# IRGate.net
KiCad netlist of a schematic drawn in EAGLE
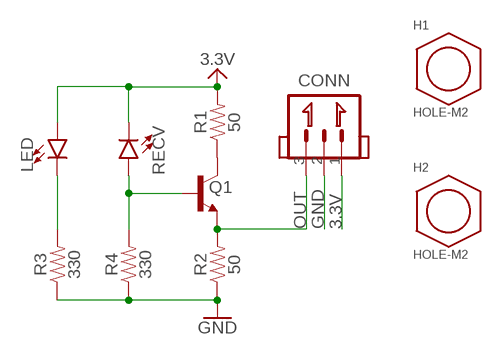
[diagram p0: schematic, sheet 1]

(export (version "E")
  (design (tool "Eeschema 10.0.6"))
  (components
    (comp (ref "CONN")
      (value "JST_1.25_3P")
      (footprint "eagle-import:JST1.25_3P")
      (libsource (lib "eagle-import") (part "JST_1.25_3P"))
    )
    (comp (ref "H1")
      (value "HOLE-M2")
      (footprint "eagle-import:M2")
      (libsource (lib "eagle-import") (part "HOLE-M2"))
    )
    (comp (ref "H2")
      (value "HOLE-M2")
      (footprint "eagle-import:M2")
      (libsource (lib "eagle-import") (part "HOLE-M2"))
    )
    (comp (ref "LED")
      (value "LED-IRTSAL6100")
      (footprint "eagle-import:LED_5MM")
      (libsource (lib "eagle-import") (part "LED-IRTSAL6100"))
    )
    (comp (ref "Q1")
      (value "NPNSOT23-3")
      (footprint "eagle-import:SOT23-3")
      (libsource (lib "eagle-import") (part "NPNSOT23-3"))
    )
    (comp (ref "R1")
      (value "50")
      (footprint "eagle-import:0603")
      (libsource (lib "eagle-import") (part "RESISTOR0603"))
    )
    (comp (ref "R2")
      (value "50")
      (footprint "eagle-import:0603")
      (libsource (lib "eagle-import") (part "RESISTOR0603"))
    )
    (comp (ref "R3")
      (value "330")
      (footprint "eagle-import:0603")
      (libsource (lib "eagle-import") (part "RESISTOR0603"))
    )
    (comp (ref "R4")
      (value "330")
      (footprint "eagle-import:0603")
      (libsource (lib "eagle-import") (part "RESISTOR0603"))
    )
    (comp (ref "RECV")
      (value "LED-IRSIDE_EMITTER")
      (footprint "eagle-import:LTE-302")
      (libsource (lib "eagle-import") (part "LED-IRSIDE_EMITTER"))
    )
  )
  (nets
    (net (code "1") (name "/OUT") (class "Default")
      (node (ref "CONN") (pin "3") (pinfunction "3_3") (pintype "passive"))
      (node (ref "Q1") (pin "2") (pinfunction "E_2") (pintype "passive"))
      (node (ref "R2") (pin "2") (pinfunction "2_2") (pintype "passive"))
    )
    (net (code "2") (name "Net-(LED-C)") (class "Default")
      (node (ref "LED") (pin "K") (pinfunction "C_K") (pintype "passive"))
      (node (ref "R3") (pin "2") (pinfunction "2_2") (pintype "passive"))
    )
    (net (code "3") (name "Net-(Q1-B)") (class "Default")
      (node (ref "Q1") (pin "1") (pinfunction "B_1") (pintype "passive"))
      (node (ref "R4") (pin "2") (pinfunction "2_2") (pintype "passive"))
      (node (ref "RECV") (pin "A") (pinfunction "A_A") (pintype "passive"))
    )
    (net (code "4") (name "Net-(Q1-C)") (class "Default")
      (node (ref "Q1") (pin "3") (pinfunction "C_3") (pintype "passive"))
      (node (ref "R1") (pin "1") (pinfunction "1_1") (pintype "passive"))
    )
    (net (code "5") (name "SUPPLY_3.3V") (class "Default")
      (node (ref "CONN") (pin "1") (pinfunction "1_1") (pintype "passive"))
      (node (ref "LED") (pin "A") (pinfunction "A_A") (pintype "passive"))
      (node (ref "R1") (pin "2") (pinfunction "2_2") (pintype "passive"))
      (node (ref "RECV") (pin "C") (pinfunction "C_C") (pintype "passive"))
    )
    (net (code "6") (name "SUPPLY_GND") (class "Default")
      (node (ref "CONN") (pin "2") (pinfunction "2_2") (pintype "passive"))
      (node (ref "R2") (pin "1") (pinfunction "1_1") (pintype "passive"))
      (node (ref "R3") (pin "1") (pinfunction "1_1") (pintype "passive"))
      (node (ref "R4") (pin "1") (pinfunction "1_1") (pintype "passive"))
    )
  )
)
